# 09_USB_HUB.net
KiCad netlist of a schematic drawn in Altium Designer
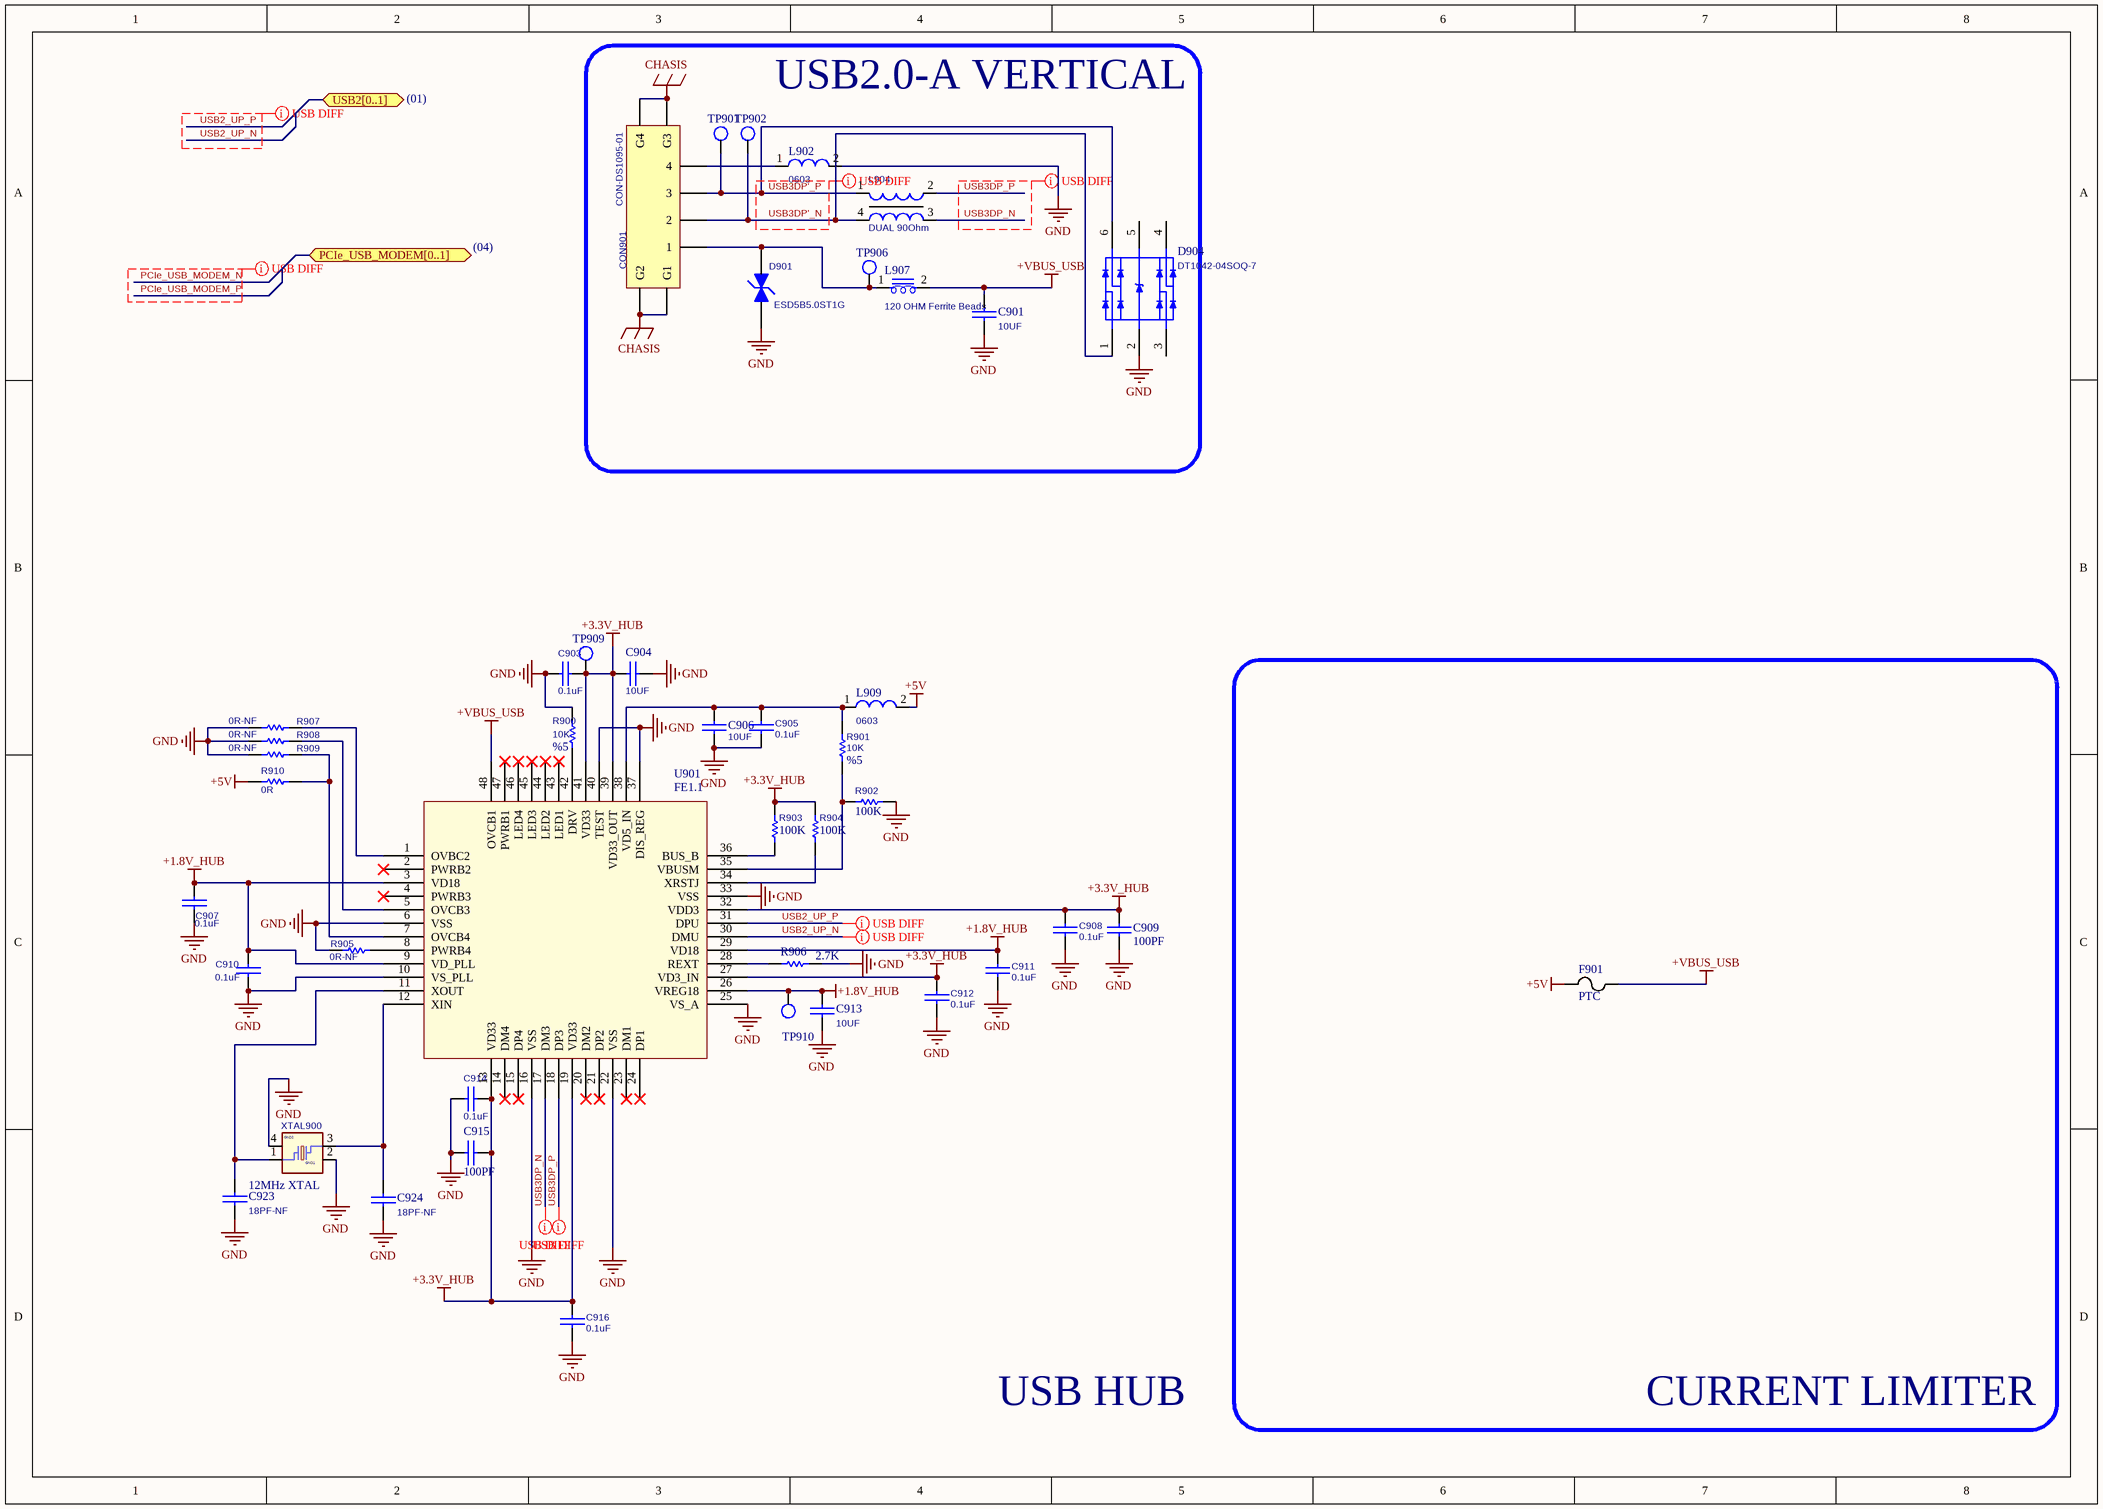
[diagram p0: 09 USB HUB.SchDoc]

(export (version "E")
  (design (tool "Eeschema 10.0.6"))
  (components
    (comp (ref "C901")
      (value "10UF")
      (footprint "0805")
      (description "CAP CER 10UF 16V X5R 0805")
      (fields (field (name "CREATED BY") "EE") (field (name "CHECKED BY") "*"))
      (libsource (lib "ARETE_SCH") (part "CAP-CL21A106KOQNNNG"))
    )
    (comp (ref "C903")
      (value "0.1uF")
      (footprint "0402_CC")
      (description "CAP VER 0.1UF 16V X7R 0402")
      (fields (field (name "CREATED BY") "LA") (field (name "CHECKED BY") "*"))
      (libsource (lib "ARETE_SCH") (part "CAP-CL05B104KO5NNNC"))
    )
    (comp (ref "C904")
      (value "10UF")
      (footprint "0805")
      (description "CAP CER 10UF 16V X5R 0805")
      (fields (field (name "CREATED BY") "EE") (field (name "CHECKED BY") "*"))
      (libsource (lib "ARETE_SCH") (part "CAP-CL21A106KOQNNNG"))
    )
    (comp (ref "C905")
      (value "0.1uF")
      (footprint "0402_CC")
      (description "CAP VER 0.1UF 16V X7R 0402")
      (fields (field (name "CREATED BY") "LA") (field (name "CHECKED BY") "*"))
      (libsource (lib "ARETE_SCH") (part "CAP-CL05B104KO5NNNC"))
    )
    (comp (ref "C906")
      (value "10UF")
      (footprint "0805")
      (description "CAP CER 10UF 16V X5R 0805")
      (fields (field (name "CREATED BY") "EE") (field (name "CHECKED BY") "*"))
      (libsource (lib "ARETE_SCH") (part "CAP-CL21A106KOQNNNG"))
    )
    (comp (ref "C907")
      (value "0.1uF")
      (footprint "0402_CC")
      (description "CAP VER 0.1UF 16V X7R 0402")
      (fields (field (name "CREATED BY") "LA") (field (name "CHECKED BY") "*"))
      (libsource (lib "ARETE_SCH") (part "CAP-CL05B104KO5NNNC"))
    )
    (comp (ref "C908")
      (value "0.1uF")
      (footprint "0402_CC")
      (description "CAP VER 0.1UF 16V X7R 0402")
      (fields (field (name "CREATED BY") "LA") (field (name "CHECKED BY") "*"))
      (libsource (lib "ARETE_SCH") (part "CAP-CL05B104KO5NNNC"))
    )
    (comp (ref "C909")
      (value "100PF")
      (footprint "0402_CC")
      (description "CAP CER 100PF 50V C0G/NPO 0402")
      (fields (field (name "CREATED BY") "*") (field (name "CHECKED BY") "*"))
      (libsource (lib "ARETE_SCH") (part "CAP-CC0402JRNPO9BN101"))
    )
    (comp (ref "C910")
      (value "0.1uF")
      (footprint "0402_CC")
      (description "CAP VER 0.1UF 16V X7R 0402")
      (fields (field (name "CREATED BY") "LA") (field (name "CHECKED BY") "*"))
      (libsource (lib "ARETE_SCH") (part "CAP-CL05B104KO5NNNC"))
    )
    (comp (ref "C911")
      (value "0.1uF")
      (footprint "0402_CC")
      (description "CAP VER 0.1UF 16V X7R 0402")
      (fields (field (name "CREATED BY") "LA") (field (name "CHECKED BY") "*"))
      (libsource (lib "ARETE_SCH") (part "CAP-CL05B104KO5NNNC"))
    )
    (comp (ref "C912")
      (value "0.1uF")
      (footprint "0402_CC")
      (description "CAP VER 0.1UF 16V X7R 0402")
      (fields (field (name "CREATED BY") "LA") (field (name "CHECKED BY") "*"))
      (libsource (lib "ARETE_SCH") (part "CAP-CL05B104KO5NNNC"))
    )
    (comp (ref "C913")
      (value "10UF")
      (footprint "0805")
      (description "CAP CER 10UF 16V X5R 0805")
      (fields (field (name "CREATED BY") "EE") (field (name "CHECKED BY") "*"))
      (libsource (lib "ARETE_SCH") (part "CAP-CL21A106KOQNNNG"))
    )
    (comp (ref "C914")
      (value "0.1uF")
      (footprint "0402_CC")
      (description "CAP VER 0.1UF 16V X7R 0402")
      (fields (field (name "CREATED BY") "LA") (field (name "CHECKED BY") "*"))
      (libsource (lib "ARETE_SCH") (part "CAP-CL05B104KO5NNNC"))
    )
    (comp (ref "C915")
      (value "100PF")
      (footprint "0402_CC")
      (description "CAP CER 100PF 50V C0G/NPO 0402")
      (fields (field (name "CREATED BY") "*") (field (name "CHECKED BY") "*"))
      (libsource (lib "ARETE_SCH") (part "CAP-CC0402JRNPO9BN101"))
    )
    (comp (ref "C916")
      (value "0.1uF")
      (footprint "0402_CC")
      (description "CAP VER 0.1UF 16V X7R 0402")
      (fields (field (name "CREATED BY") "LA") (field (name "CHECKED BY") "*"))
      (libsource (lib "ARETE_SCH") (part "CAP-CL05B104KO5NNNC"))
    )
    (comp (ref "C923")
      (value "18PF-NF")
      (footprint "0402_CC")
      (description "CAP CER 18PF 50V C0G/NP0 0402")
      (fields (field (name "CREATED BY") "*") (field (name "CHECKED BY") "*"))
      (libsource (lib "ARETE_SCH") (part "CAP-GCM1555C1H180JA16D"))
    )
    (comp (ref "C924")
      (value "18PF-NF")
      (footprint "0402_CC")
      (description "CAP CER 18PF 50V C0G/NP0 0402")
      (fields (field (name "CREATED BY") "*") (field (name "CHECKED BY") "*"))
      (libsource (lib "ARETE_SCH") (part "CAP-GCM1555C1H180JA16D"))
    )
    (comp (ref "CON901")
      (value "CON-DS1095-01")
      (footprint "CON-DS1095-01")
      (description "CON USB2.0 A TYPE VERTICAL TYPE TH")
      (fields (field (name "CREATED BY") "LA") (field (name "CHECKED BY") "*"))
      (libsource (lib "ARETE_SCH") (part "CON-DS1095-01"))
    )
    (comp (ref "D901")
      (value "ESD5B5.0ST1G")
      (footprint "SOD523 - SZESD")
      (description "VS DIODE 5V SOD523")
      (fields (field (name "CREATED BY") "E.E") (field (name "CHECKED BY") "*"))
      (libsource (lib "ARETE_SCH") (part "DIODE-ESD5B5.0ST1G"))
    )
    (comp (ref "D904")
      (value "DT1042-04SOQ-7")
      (footprint "DIODE-DT1042-04SOQ-7")
      (description "HDMI TVS DIODE")
      (fields (field (name "CREATED BY") "E.E") (field (name "CHECKED BY") "*"))
      (libsource (lib "ARETE_SCH") (part "DIODE-DT1042-04SOQ-7"))
    )
    (comp (ref "F901")
      (value "PTC")
      (footprint "1812")
      (description "THERMISTOR PTC RESETTABLE FUSE 1206 1100mA 33V 1812")
      (fields (field (name "CREATED BY") "EE") (field (name "CHECKED BY") "*"))
      (libsource (lib "ARETE_V2_SCH") (part "FUSE-KMC5S110RY33"))
    )
    (comp (ref "L902")
      (value "0603")
      (footprint "0603_RES")
      (description "0OHM 0603")
      (fields (field (name "CREATED BY") "EE") (field (name "CHECKED BY") "*"))
      (libsource (lib "ARETE_SCH") (part "IND-FERRITE (RES 0 OHM) 0603"))
    )
    (comp (ref "L904")
      (value "DUAL 90Ohm")
      (footprint "DLW21H")
      (description "Common Mode Chokes Dual 90Ohm 100MHz 0.33A 0.35Ohm DCR SMD T/R")
      (fields (field (name "CREATED BY") "E.E") (field (name "CHECKED BY") "*"))
      (libsource (lib "ARETE_SCH") (part "IND-DLW21HN900SQ2L"))
    )
    (comp (ref "L907")
      (value "120 OHM Ferrite Beads")
      (footprint "0603_RES")
      (description "Ferrite Beads Multi-Layer 120Ohm 25% 100MHz 2A 0.05Ohm DCR 0603 Automotive T/R")
      (fields (field (name "CREATED BY") "E.E") (field (name "CHECKED BY") "*"))
      (libsource (lib "ARETE_SCH") (part "IND-BLM18PG121SH1D"))
    )
    (comp (ref "L909")
      (value "0603")
      (footprint "0603_RES")
      (description "0OHM 0603")
      (fields (field (name "CREATED BY") "EE") (field (name "CHECKED BY") "*"))
      (libsource (lib "ARETE_SCH") (part "IND-FERRITE (RES 0 OHM) 0603"))
    )
    (comp (ref "R900")
      (value "10K")
      (footprint "0402_RES")
      (description "RES 10K OHM 5% 1/16W 0402")
      (fields
        (field (name "TOLERANCE") "%5")
        (field (name "CREATED BY") "LA")
        (field (name "CHECKED BY") "*")
      )
      (libsource (lib "ARETE_SCH") (part "RES-RMCF0402JT10K0"))
    )
    (comp (ref "R901")
      (value "10K")
      (footprint "0402_RES")
      (description "RES 10K OHM 5% 1/16W 0402")
      (fields
        (field (name "TOLERANCE") "%5")
        (field (name "CREATED BY") "LA")
        (field (name "CHECKED BY") "*")
      )
      (libsource (lib "ARETE_SCH") (part "RES-RMCF0402JT10K0"))
    )
    (comp (ref "R902")
      (value "100K")
      (footprint "0402_RES")
      (description "RES 100K OHM 5% 1/16W 0402")
      (fields
        (field (name "TOLERANCE") "%5")
        (field (name "CREATED BY") "LA")
        (field (name "CHECKED BY") "*")
      )
      (libsource (lib "ARETE_SCH") (part "RES-RMCF0402JT100K"))
    )
    (comp (ref "R903")
      (value "100K")
      (footprint "0402_RES")
      (description "RES 100K OHM 5% 1/16W 0402")
      (fields
        (field (name "TOLERANCE") "%5")
        (field (name "CREATED BY") "LA")
        (field (name "CHECKED BY") "*")
      )
      (libsource (lib "ARETE_SCH") (part "RES-RMCF0402JT100K"))
    )
    (comp (ref "R904")
      (value "100K")
      (footprint "0402_RES")
      (description "RES 100K OHM 5% 1/16W 0402")
      (fields
        (field (name "TOLERANCE") "%5")
        (field (name "CREATED BY") "LA")
        (field (name "CHECKED BY") "*")
      )
      (libsource (lib "ARETE_SCH") (part "RES-RMCF0402JT100K"))
    )
    (comp (ref "R905")
      (value "0R-NF")
      (footprint "0402_RES")
      (description "RES 0 OHM JUMPER 1/16W 0402")
      (fields (field (name "CREATED BY") "LA") (field (name "CHECKED BY") "*"))
      (libsource (lib "ARETE_SCH") (part "RES-RMCF0402ZT0R00"))
    )
    (comp (ref "R906")
      (value "2.7K")
      (footprint "0402_RES")
      (description "RES SMD 2.7K OHM 1% 1/16W 0402")
      (fields (field (name "CREATED BY") "EE") (field (name "CHECKED BY") "*"))
      (libsource (lib "ARETE_V2_SCH") (part "RES-RMCF0402FT2K70"))
    )
    (comp (ref "R907")
      (value "0R-NF")
      (footprint "0402_RES")
      (description "RES 0 OHM JUMPER 1/16W 0402")
      (fields (field (name "CREATED BY") "LA") (field (name "CHECKED BY") "*"))
      (libsource (lib "ARETE_SCH") (part "RES-RMCF0402ZT0R00"))
    )
    (comp (ref "R908")
      (value "0R-NF")
      (footprint "0402_RES")
      (description "RES 0 OHM JUMPER 1/16W 0402")
      (fields (field (name "CREATED BY") "LA") (field (name "CHECKED BY") "*"))
      (libsource (lib "ARETE_SCH") (part "RES-RMCF0402ZT0R00"))
    )
    (comp (ref "R909")
      (value "0R-NF")
      (footprint "0402_RES")
      (description "RES 0 OHM JUMPER 1/16W 0402")
      (fields (field (name "CREATED BY") "LA") (field (name "CHECKED BY") "*"))
      (libsource (lib "ARETE_SCH") (part "RES-RMCF0402ZT0R00"))
    )
    (comp (ref "R910")
      (value "0R")
      (footprint "0402_RES")
      (description "RES 0 OHM JUMPER 1/16W 0402")
      (fields (field (name "CREATED BY") "LA") (field (name "CHECKED BY") "*"))
      (libsource (lib "ARETE_SCH") (part "RES-RMCF0402ZT0R00"))
    )
    (comp (ref "TP901")
      (value "TEST POINT 15")
      (footprint "testpoint_15")
      (libsource (lib "ARETE_L") (part "TEST POINT 15"))
    )
    (comp (ref "TP902")
      (value "TEST POINT 15")
      (footprint "testpoint_15")
      (libsource (lib "ARETE_L") (part "TEST POINT 15"))
    )
    (comp (ref "TP906")
      (value "TEST POINT 15")
      (footprint "testpoint_15")
      (libsource (lib "ARETE_L") (part "TEST POINT 15"))
    )
    (comp (ref "TP909")
      (value "TEST POINT 15")
      (footprint "testpoint_15")
      (libsource (lib "ARETE_L") (part "TEST POINT 15"))
    )
    (comp (ref "TP910")
      (value "TEST POINT 15")
      (footprint "testpoint_15")
      (libsource (lib "ARETE_L") (part "TEST POINT 15"))
    )
    (comp (ref "U901")
      (value "FE1.1")
      (footprint "LQFP48")
      (description "IC 4XCH USB Hub Controller USB 2.0 USB Interface 48-QFP (7x7)")
      (fields (field (name "CREATED BY") "OKS") (field (name "CHECKED BY") "*"))
      (libsource (lib "ARETE_V2_SCH") (part "IC-FE1.1-AQFP48A"))
    )
    (comp (ref "XTAL900")
      (value "CRYSTAL 12.MHZ 18PF SMD")
      (footprint "XTLOSC4_3P2X2P5MM_SM")
      (description "CRYSTAL 12.0000MHZ 18PF SMD")
      (fields (field (name "CREATED BY") "E.E") (field (name "CHECKED BY") "*"))
      (libsource (lib "ARETE_SCH") (part "XTAL-FA-238V 12.0000MB50X-C0"))
    )
  )
  (nets
    (net (code "5") (name "+1.8V_HUB") (class "Default")
      (node (ref "C907") (pin "1") (pinfunction "1_1") (pintype "passive"))
      (node (ref "C910") (pin "1") (pinfunction "1_1") (pintype "passive"))
      (node (ref "C911") (pin "2") (pinfunction "2_2") (pintype "passive"))
      (node (ref "C913") (pin "1") (pinfunction "1_1") (pintype "passive"))
      (node (ref "TP910") (pin "1") (pinfunction "1_1") (pintype "passive"))
      (node (ref "U901") (pin "26") (pinfunction "VREG18_26") (pintype "passive"))
      (node (ref "U901") (pin "29") (pinfunction "VD18_29") (pintype "passive"))
      (node (ref "U901") (pin "3") (pinfunction "VD18_3") (pintype "passive"))
      (node (ref "U901") (pin "9") (pinfunction "VD_PLL_9") (pintype "passive"))
    )
    (net (code "6") (name "+3.3V_HUB") (class "Default")
      (node (ref "C903") (pin "1") (pinfunction "1_1") (pintype "passive"))
      (node (ref "C904") (pin "1") (pinfunction "1_1") (pintype "passive"))
      (node (ref "C908") (pin "2") (pinfunction "2_2") (pintype "passive"))
      (node (ref "C909") (pin "2") (pinfunction "2_2") (pintype "passive"))
      (node (ref "C912") (pin "2") (pinfunction "2_2") (pintype "passive"))
      (node (ref "C914") (pin "2") (pinfunction "2_2") (pintype "passive"))
      (node (ref "C915") (pin "2") (pinfunction "2_2") (pintype "passive"))
      (node (ref "C916") (pin "2") (pinfunction "2_2") (pintype "passive"))
      (node (ref "R903") (pin "2") (pinfunction "2_2") (pintype "passive"))
      (node (ref "R904") (pin "2") (pinfunction "2_2") (pintype "passive"))
      (node (ref "TP909") (pin "1") (pinfunction "1_1") (pintype "passive"))
      (node (ref "U901") (pin "13") (pinfunction "VD33_13") (pintype "passive"))
      (node (ref "U901") (pin "19") (pinfunction "VD33_19") (pintype "passive"))
      (node (ref "U901") (pin "27") (pinfunction "VD3_IN_27") (pintype "passive"))
      (node (ref "U901") (pin "32") (pinfunction "VDD3_32") (pintype "passive"))
      (node (ref "U901") (pin "39") (pinfunction "VD33_OUT_39") (pintype "passive"))
      (node (ref "U901") (pin "41") (pinfunction "VD33_41") (pintype "passive"))
    )
    (net (code "7") (name "+5V") (class "Default")
      (node (ref "F901") (pin "1") (pinfunction "1_1") (pintype "passive"))
      (node (ref "L909") (pin "2") (pinfunction "2_2") (pintype "passive"))
      (node (ref "R910") (pin "2") (pinfunction "2_2") (pintype "passive"))
    )
    (net (code "8") (name "+VBUS_USB") (class "Default")
      (node (ref "C901") (pin "1") (pinfunction "1_1") (pintype "passive"))
      (node (ref "F901") (pin "2") (pinfunction "2_2") (pintype "passive"))
      (node (ref "L907") (pin "2") (pinfunction "2_2") (pintype "passive"))
      (node (ref "U901") (pin "48") (pinfunction "OVCB1_48") (pintype "passive"))
    )
    (net (code "13") (name "/USB2_UP_N") (class "Default")
      (node (ref "U901") (pin "30") (pinfunction "DMU_30") (pintype "passive"))
    )
    (net (code "14") (name "/USB2_UP_P") (class "Default")
      (node (ref "U901") (pin "31") (pinfunction "DPU_31") (pintype "passive"))
    )
    (net (code "15") (name "/USB3DP'_N") (class "Default")
      (node (ref "CON901") (pin "2") (pinfunction "2_2") (pintype "passive"))
      (node (ref "D904") (pin "1") (pinfunction "IO1_1") (pintype "passive"))
      (node (ref "L904") (pin "4") (pinfunction "4_4") (pintype "passive"))
      (node (ref "TP902") (pin "1") (pinfunction "1_1") (pintype "passive"))
    )
    (net (code "16") (name "/USB3DP'_P") (class "Default")
      (node (ref "CON901") (pin "3") (pinfunction "3_3") (pintype "passive"))
      (node (ref "D904") (pin "6") (pinfunction "IO4_6") (pintype "passive"))
      (node (ref "L904") (pin "1") (pinfunction "1_1") (pintype "passive"))
      (node (ref "TP901") (pin "1") (pinfunction "1_1") (pintype "passive"))
    )
    (net (code "17") (name "/USB3DP_N") (class "Default")
      (node (ref "L904") (pin "3") (pinfunction "3_3") (pintype "passive"))
      (node (ref "U901") (pin "17") (pinfunction "DM3_17") (pintype "passive"))
    )
    (net (code "18") (name "/USB3DP_P") (class "Default")
      (node (ref "L904") (pin "2") (pinfunction "2_2") (pintype "passive"))
      (node (ref "U901") (pin "18") (pinfunction "DP3_18") (pintype "passive"))
    )
    (net (code "19") (name "CHASIS") (class "Default")
      (node (ref "CON901") (pin "G1") (pinfunction "G1_G1") (pintype "passive"))
      (node (ref "CON901") (pin "G2") (pinfunction "G2_G2") (pintype "passive"))
      (node (ref "CON901") (pin "G3") (pinfunction "G3_G3") (pintype "passive"))
      (node (ref "CON901") (pin "G4") (pinfunction "G4_G4") (pintype "passive"))
    )
    (net (code "20") (name "GND") (class "Default")
      (node (ref "C901") (pin "2") (pinfunction "2_2") (pintype "passive"))
      (node (ref "C903") (pin "2") (pinfunction "2_2") (pintype "passive"))
      (node (ref "C904") (pin "2") (pinfunction "2_2") (pintype "passive"))
      (node (ref "C905") (pin "1") (pinfunction "1_1") (pintype "passive"))
      (node (ref "C906") (pin "1") (pinfunction "1_1") (pintype "passive"))
      (node (ref "C907") (pin "2") (pinfunction "2_2") (pintype "passive"))
      (node (ref "C908") (pin "1") (pinfunction "1_1") (pintype "passive"))
      (node (ref "C909") (pin "1") (pinfunction "1_1") (pintype "passive"))
      (node (ref "C910") (pin "2") (pinfunction "2_2") (pintype "passive"))
      (node (ref "C911") (pin "1") (pinfunction "1_1") (pintype "passive"))
      (node (ref "C912") (pin "1") (pinfunction "1_1") (pintype "passive"))
      (node (ref "C913") (pin "2") (pinfunction "2_2") (pintype "passive"))
      (node (ref "C914") (pin "1") (pinfunction "1_1") (pintype "passive"))
      (node (ref "C915") (pin "1") (pinfunction "1_1") (pintype "passive"))
      (node (ref "C916") (pin "1") (pinfunction "1_1") (pintype "passive"))
      (node (ref "C923") (pin "2") (pinfunction "2_2") (pintype "passive"))
      (node (ref "C924") (pin "2") (pinfunction "2_2") (pintype "passive"))
      (node (ref "D901") (pin "1") (pinfunction "A_1") (pintype "passive"))
      (node (ref "D904") (pin "2") (pinfunction "VSS_2") (pintype "power_in"))
      (node (ref "L902") (pin "2") (pinfunction "2_2") (pintype "passive"))
      (node (ref "R900") (pin "1") (pinfunction "1_1") (pintype "passive"))
      (node (ref "R902") (pin "1") (pinfunction "1_1") (pintype "passive"))
      (node (ref "R905") (pin "1") (pinfunction "1_1") (pintype "passive"))
      (node (ref "R906") (pin "2") (pinfunction "2_2") (pintype "passive"))
      (node (ref "R907") (pin "1") (pinfunction "1_1") (pintype "passive"))
      (node (ref "R908") (pin "1") (pinfunction "1_1") (pintype "passive"))
      (node (ref "R909") (pin "1") (pinfunction "1_1") (pintype "passive"))
      (node (ref "U901") (pin "10") (pinfunction "VS_PLL_10") (pintype "passive"))
      (node (ref "U901") (pin "16") (pinfunction "VSS_16") (pintype "passive"))
      (node (ref "U901") (pin "22") (pinfunction "VSS_22") (pintype "passive"))
      (node (ref "U901") (pin "25") (pinfunction "VS_A_25") (pintype "passive"))
      (node (ref "U901") (pin "33") (pinfunction "VSS_33") (pintype "passive"))
      (node (ref "U901") (pin "37") (pinfunction "DIS_REG_37") (pintype "passive"))
      (node (ref "U901") (pin "40") (pinfunction "TEST_40") (pintype "passive"))
      (node (ref "U901") (pin "6") (pinfunction "VSS_6") (pintype "passive"))
      (node (ref "XTAL900") (pin "2") (pinfunction "GND1_2") (pintype "power_in"))
      (node (ref "XTAL900") (pin "4") (pinfunction "GND2_4") (pintype "power_in"))
    )
    (net (code "21") (name "Net-(CON901-Pad4)") (class "Default")
      (node (ref "CON901") (pin "4") (pinfunction "4_4") (pintype "passive"))
      (node (ref "L902") (pin "1") (pinfunction "1_1") (pintype "passive"))
    )
    (net (code "22") (name "Net-(D901-K)") (class "Default")
      (node (ref "CON901") (pin "1") (pinfunction "1_1") (pintype "passive"))
      (node (ref "D901") (pin "2") (pinfunction "K_2") (pintype "passive"))
      (node (ref "L907") (pin "1") (pinfunction "1_1") (pintype "passive"))
      (node (ref "TP906") (pin "1") (pinfunction "1_1") (pintype "passive"))
    )
    (net (code "23") (name "Net-(U901-BUS_B)") (class "Default")
      (node (ref "R903") (pin "1") (pinfunction "1_1") (pintype "passive"))
      (node (ref "U901") (pin "36") (pinfunction "BUS_B_36") (pintype "passive"))
    )
    (net (code "24") (name "Net-(U901-DRV)") (class "Default")
      (node (ref "R900") (pin "2") (pinfunction "2_2") (pintype "passive"))
      (node (ref "U901") (pin "42") (pinfunction "DRV_42") (pintype "passive"))
    )
    (net (code "25") (name "Net-(U901-OVBC2)") (class "Default")
      (node (ref "R907") (pin "2") (pinfunction "2_2") (pintype "passive"))
      (node (ref "U901") (pin "1") (pinfunction "OVBC2_1") (pintype "passive"))
    )
    (net (code "26") (name "Net-(U901-OVCB3)") (class "Default")
      (node (ref "R908") (pin "2") (pinfunction "2_2") (pintype "passive"))
      (node (ref "U901") (pin "5") (pinfunction "OVCB3_5") (pintype "passive"))
    )
    (net (code "27") (name "Net-(U901-OVCB4)") (class "Default")
      (node (ref "R909") (pin "2") (pinfunction "2_2") (pintype "passive"))
      (node (ref "R910") (pin "1") (pinfunction "1_1") (pintype "passive"))
      (node (ref "U901") (pin "7") (pinfunction "OVCB4_7") (pintype "passive"))
    )
    (net (code "28") (name "Net-(U901-PWRB4)") (class "Default")
      (node (ref "R905") (pin "2") (pinfunction "2_2") (pintype "passive"))
      (node (ref "U901") (pin "8") (pinfunction "PWRB4_8") (pintype "passive"))
    )
    (net (code "29") (name "Net-(U901-REXT)") (class "Default")
      (node (ref "R906") (pin "1") (pinfunction "1_1") (pintype "passive"))
      (node (ref "U901") (pin "28") (pinfunction "REXT_28") (pintype "passive"))
    )
    (net (code "30") (name "Net-(U901-VBUSM)") (class "Default")
      (node (ref "R901") (pin "1") (pinfunction "1_1") (pintype "passive"))
      (node (ref "R902") (pin "2") (pinfunction "2_2") (pintype "passive"))
      (node (ref "U901") (pin "35") (pinfunction "VBUSM_35") (pintype "passive"))
    )
    (net (code "31") (name "Net-(U901-VD5_IN)") (class "Default")
      (node (ref "C905") (pin "2") (pinfunction "2_2") (pintype "passive"))
      (node (ref "C906") (pin "2") (pinfunction "2_2") (pintype "passive"))
      (node (ref "L909") (pin "1") (pinfunction "1_1") (pintype "passive"))
      (node (ref "R901") (pin "2") (pinfunction "2_2") (pintype "passive"))
      (node (ref "U901") (pin "38") (pinfunction "VD5_IN_38") (pintype "passive"))
    )
    (net (code "32") (name "Net-(U901-XIN)") (class "Default")
      (node (ref "C924") (pin "1") (pinfunction "1_1") (pintype "passive"))
      (node (ref "U901") (pin "12") (pinfunction "XIN_12") (pintype "passive"))
      (node (ref "XTAL900") (pin "3") (pinfunction "3_3") (pintype "passive"))
    )
    (net (code "33") (name "Net-(U901-XOUT)") (class "Default")
      (node (ref "C923") (pin "1") (pinfunction "1_1") (pintype "passive"))
      (node (ref "U901") (pin "11") (pinfunction "XOUT_11") (pintype "passive"))
      (node (ref "XTAL900") (pin "1") (pinfunction "1_1") (pintype "passive"))
    )
    (net (code "34") (name "Net-(U901-XRSTJ)") (class "Default")
      (node (ref "R904") (pin "1") (pinfunction "1_1") (pintype "passive"))
      (node (ref "U901") (pin "34") (pinfunction "XRSTJ_34") (pintype "passive"))
    )
    (net (code "35") (name "unconnected-(D904-IO2-Pad3)") (class "Default")
      (node (ref "D904") (pin "3") (pinfunction "IO2_3") (pintype "passive"))
    )
    (net (code "36") (name "unconnected-(D904-IO3-Pad4)") (class "Default")
      (node (ref "D904") (pin "4") (pinfunction "IO3_4") (pintype "passive"))
    )
    (net (code "37") (name "unconnected-(D904-VCC-Pad5)") (class "Default")
      (node (ref "D904") (pin "5") (pinfunction "VCC_5") (pintype "power_in"))
    )
    (net (code "38") (name "unconnected-(U901-DM1-Pad23)") (class "Default")
      (node (ref "U901") (pin "23") (pinfunction "DM1_23") (pintype "passive+no_connect"))
    )
    (net (code "39") (name "unconnected-(U901-DM2-Pad20)") (class "Default")
      (node (ref "U901") (pin "20") (pinfunction "DM2_20") (pintype "passive+no_connect"))
    )
    (net (code "40") (name "unconnected-(U901-DM4-Pad14)") (class "Default")
      (node (ref "U901") (pin "14") (pinfunction "DM4_14") (pintype "passive+no_connect"))
    )
    (net (code "41") (name "unconnected-(U901-DP1-Pad24)") (class "Default")
      (node (ref "U901") (pin "24") (pinfunction "DP1_24") (pintype "passive+no_connect"))
    )
    (net (code "42") (name "unconnected-(U901-DP2-Pad21)") (class "Default")
      (node (ref "U901") (pin "21") (pinfunction "DP2_21") (pintype "passive+no_connect"))
    )
    (net (code "43") (name "unconnected-(U901-DP4-Pad15)") (class "Default")
      (node (ref "U901") (pin "15") (pinfunction "DP4_15") (pintype "passive+no_connect"))
    )
    (net (code "44") (name "unconnected-(U901-LED1-Pad43)") (class "Default")
      (node (ref "U901") (pin "43") (pinfunction "LED1_43") (pintype "passive+no_connect"))
    )
    (net (code "45") (name "unconnected-(U901-LED2-Pad44)") (class "Default")
      (node (ref "U901") (pin "44") (pinfunction "LED2_44") (pintype "passive+no_connect"))
    )
    (net (code "46") (name "unconnected-(U901-LED3-Pad45)") (class "Default")
      (node (ref "U901") (pin "45") (pinfunction "LED3_45") (pintype "passive+no_connect"))
    )
    (net (code "47") (name "unconnected-(U901-LED4-Pad46)") (class "Default")
      (node (ref "U901") (pin "46") (pinfunction "LED4_46") (pintype "passive+no_connect"))
    )
    (net (code "48") (name "unconnected-(U901-PWRB1-Pad47)") (class "Default")
      (node (ref "U901") (pin "47") (pinfunction "PWRB1_47") (pintype "passive+no_connect"))
    )
    (net (code "49") (name "unconnected-(U901-PWRB2-Pad2)") (class "Default")
      (node (ref "U901") (pin "2") (pinfunction "PWRB2_2") (pintype "passive+no_connect"))
    )
    (net (code "50") (name "unconnected-(U901-PWRB3-Pad4)") (class "Default")
      (node (ref "U901") (pin "4") (pinfunction "PWRB3_4") (pintype "passive+no_connect"))
    )
  )
)
